# balise_mettrice_analogique.net
KiCad netlist of a schematic drawn in EAGLE
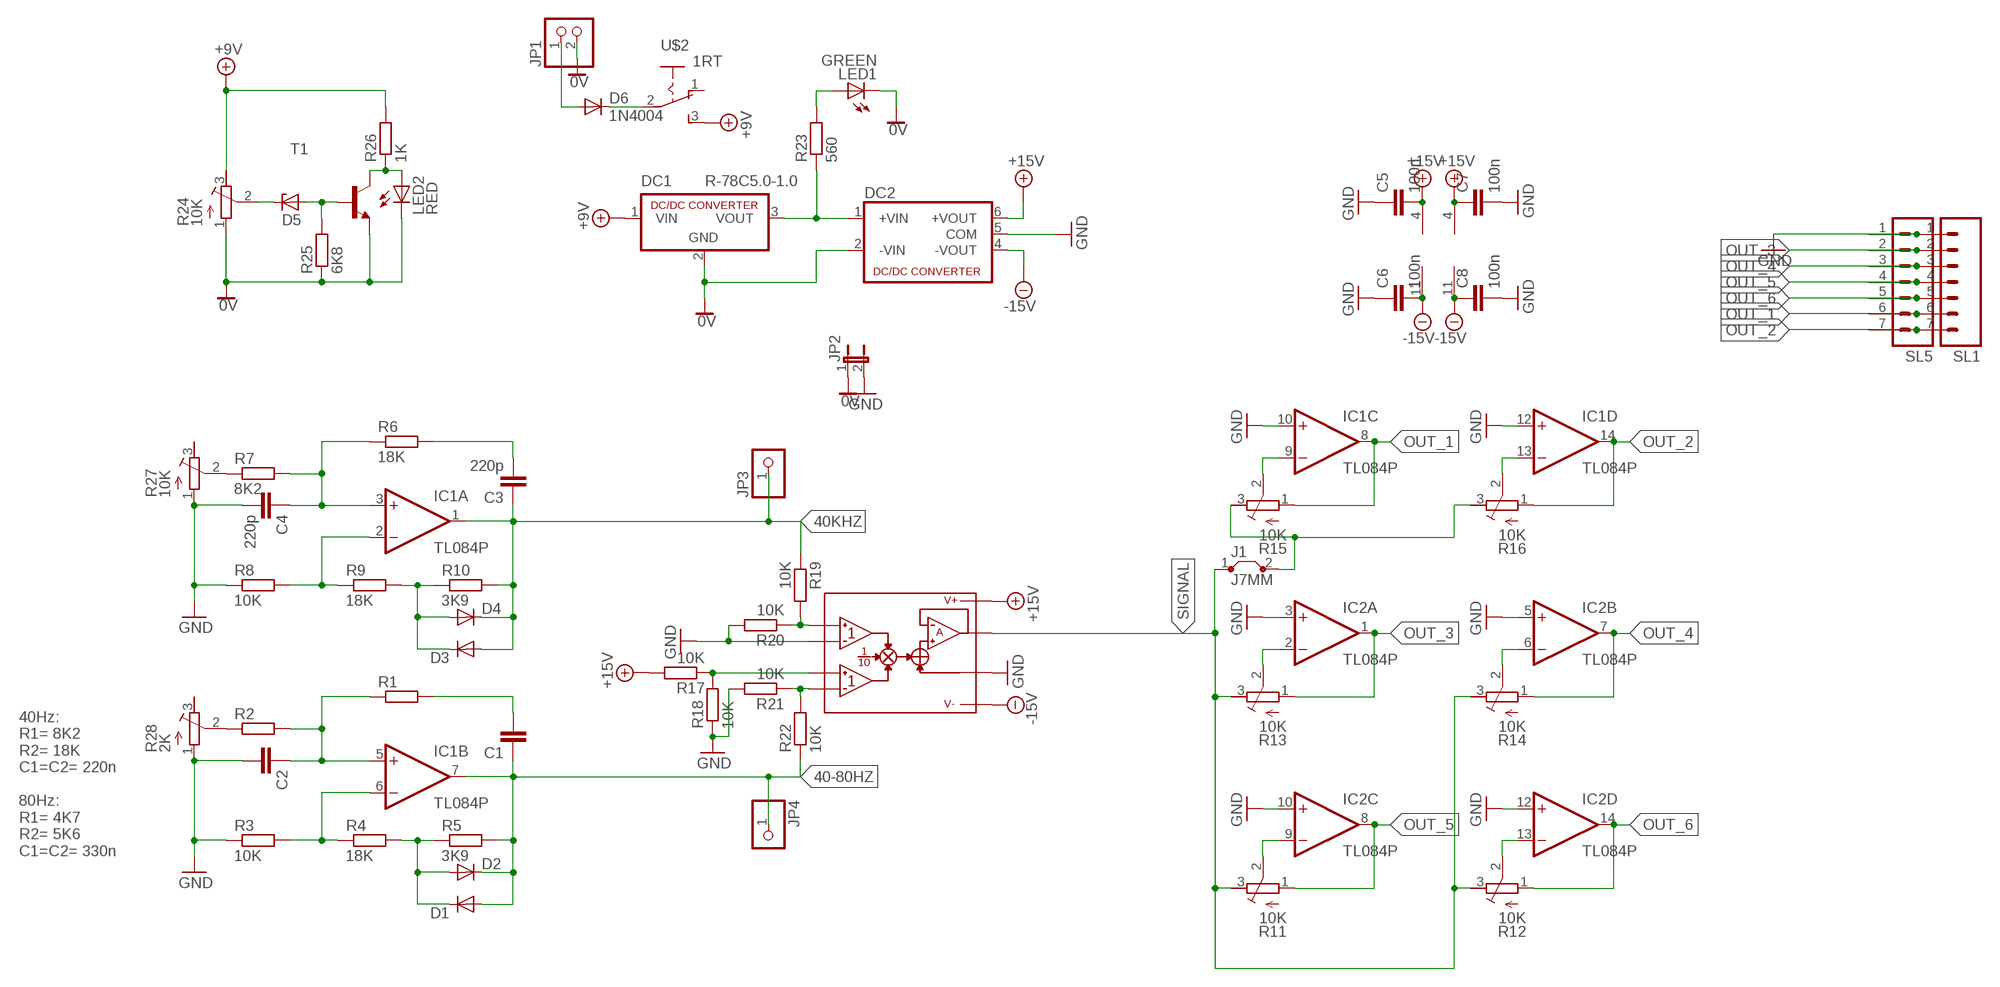
[diagram p0: schematic, sheet 1]

(export (version "E")
  (design (tool "Eeschema 10.0.6"))
  (components
    (comp (ref "C1")
      (value "C-EU075-032X103")
      (footprint "eagle-import:C075-032X103")
      (libsource (lib "eagle-import") (part "C-EU075-032X103"))
    )
    (comp (ref "C2")
      (value "C-EU075-032X103")
      (footprint "eagle-import:C075-032X103")
      (libsource (lib "eagle-import") (part "C-EU075-032X103"))
    )
    (comp (ref "C3")
      (value "220p")
      (footprint "eagle-import:C075-032X103")
      (fields (field (name "MF") "PANASONIC ELECTRONIC COMPONENTS") (field (name "MPN") "EEE1EA220SP"))
      (libsource (lib "eagle-import") (part "C-EU075-032X103"))
    )
    (comp (ref "C4")
      (value "220p")
      (footprint "eagle-import:C075-032X103")
      (fields (field (name "MF") "PANASONIC ELECTRONIC COMPONENTS") (field (name "MPN") "EEE1EA220SP"))
      (libsource (lib "eagle-import") (part "C-EU075-032X103"))
    )
    (comp (ref "C5")
      (value "100n")
      (footprint "eagle-import:C050-024X044")
      (libsource (lib "eagle-import") (part "C-EU050-024X044"))
    )
    (comp (ref "C6")
      (value "100n")
      (footprint "eagle-import:C050-024X044")
      (libsource (lib "eagle-import") (part "C-EU050-024X044"))
    )
    (comp (ref "C7")
      (value "100n")
      (footprint "eagle-import:C050-024X044")
      (libsource (lib "eagle-import") (part "C-EU050-024X044"))
    )
    (comp (ref "C8")
      (value "100n")
      (footprint "eagle-import:C050-024X044")
      (libsource (lib "eagle-import") (part "C-EU050-024X044"))
    )
    (comp (ref "D1")
      (value "DIODE-D-2.5")
      (footprint "eagle-import:D-2.5")
      (libsource (lib "eagle-import") (part "DIODE-D-2.5"))
    )
    (comp (ref "D2")
      (value "DIODE-D-2.5")
      (footprint "eagle-import:D-2.5")
      (libsource (lib "eagle-import") (part "DIODE-D-2.5"))
    )
    (comp (ref "D3")
      (value "DIODE-D-2.5")
      (footprint "eagle-import:D-2.5")
      (libsource (lib "eagle-import") (part "DIODE-D-2.5"))
    )
    (comp (ref "D4")
      (value "DIODE-D-2.5")
      (footprint "eagle-import:D-2.5")
      (libsource (lib "eagle-import") (part "DIODE-D-2.5"))
    )
    (comp (ref "D5")
      (value "ZENER-DIODEZD-2.5")
      (footprint "eagle-import:ZDIO-2.5")
      (libsource (lib "eagle-import") (part "ZENER-DIODEZD-2.5"))
    )
    (comp (ref "D6")
      (value "1N4004")
      (footprint "eagle-import:DO41-10")
      (libsource (lib "eagle-import") (part "1N4004"))
    )
    (comp (ref "DC1")
      (value "R-78C5.0-1.0")
      (footprint "eagle-import:SIP3")
      (libsource (lib "eagle-import") (part "R-78C-1.05.0"))
    )
    (comp (ref "DC2")
      (value "NMA")
      (footprint "eagle-import:NMA")
      (fields
        (field (name "MF") "C & D TECHNOLOGIES, INC")
        (field (name "MPN") "NMA0515SC")
        (field (name "MF_1") "MURATA POWER SOLUTIONS")
        (field (name "MPN_1") "NMA1205DC")
        (field (name "OC_FARNELL") "1021434")
      )
      (libsource (lib "eagle-import") (part "NMA"))
    )
    (comp (ref "IC1")
      (value "TL084P")
      (footprint "eagle-import:DIL14")
      (fields (field (name "OC_FARNELL") "unknown"))
      (libsource (lib "eagle-import") (part "TL084P"))
    )
    (comp (ref "IC2")
      (value "TL084P")
      (footprint "eagle-import:DIL14")
      (fields (field (name "OC_FARNELL") "unknown"))
      (libsource (lib "eagle-import") (part "TL084P"))
    )
    (comp (ref "J1")
      (value "J7MM")
      (footprint "eagle-import:07")
      (libsource (lib "eagle-import") (part "J7MM"))
    )
    (comp (ref "JP1")
      (value "PINHD-1X2")
      (footprint "eagle-import:1X02")
      (libsource (lib "eagle-import") (part "PINHD-1X2"))
    )
    (comp (ref "JP2")
      (value "JP1E")
      (footprint "eagle-import:JP1")
      (libsource (lib "eagle-import") (part "JP1E"))
    )
    (comp (ref "JP3")
      (value "PINHD-1X1")
      (footprint "eagle-import:1X01")
      (libsource (lib "eagle-import") (part "PINHD-1X1"))
    )
    (comp (ref "JP4")
      (value "PINHD-1X1")
      (footprint "eagle-import:1X01")
      (libsource (lib "eagle-import") (part "PINHD-1X1"))
    )
    (comp (ref "LED1")
      (value "GREEN")
      (footprint "eagle-import:Q62902-B155")
      (libsource (lib "eagle-import") (part "LEDB155"))
    )
    (comp (ref "LED2")
      (value "RED")
      (footprint "eagle-import:Q62902-B155")
      (libsource (lib "eagle-import") (part "LEDB155"))
    )
    (comp (ref "R1")
      (value "R-EU_0207/2V")
      (footprint "eagle-import:0207_2V")
      (libsource (lib "eagle-import") (part "R-EU_0207/2V"))
    )
    (comp (ref "R2")
      (value "R-EU_0204/7")
      (footprint "eagle-import:0204_7")
      (libsource (lib "eagle-import") (part "R-EU_0204/7"))
    )
    (comp (ref "R3")
      (value "10K")
      (footprint "eagle-import:0207_2V")
      (libsource (lib "eagle-import") (part "R-EU_0207/2V"))
    )
    (comp (ref "R4")
      (value "18K")
      (footprint "eagle-import:0207_2V")
      (libsource (lib "eagle-import") (part "R-EU_0207/2V"))
    )
    (comp (ref "R5")
      (value "3K9")
      (footprint "eagle-import:0207_2V")
      (libsource (lib "eagle-import") (part "R-EU_0207/2V"))
    )
    (comp (ref "R6")
      (value "18K")
      (footprint "eagle-import:0207_2V")
      (libsource (lib "eagle-import") (part "R-EU_0207/2V"))
    )
    (comp (ref "R7")
      (value "8K2")
      (footprint "eagle-import:0207_2V")
      (libsource (lib "eagle-import") (part "R-EU_0207/2V"))
    )
    (comp (ref "R8")
      (value "10K")
      (footprint "eagle-import:0207_2V")
      (libsource (lib "eagle-import") (part "R-EU_0207/2V"))
    )
    (comp (ref "R9")
      (value "18K")
      (footprint "eagle-import:0207_2V")
      (libsource (lib "eagle-import") (part "R-EU_0207/2V"))
    )
    (comp (ref "R10")
      (value "3K9")
      (footprint "eagle-import:0207_2V")
      (libsource (lib "eagle-import") (part "R-EU_0207/2V"))
    )
    (comp (ref "R11")
      (value "10K")
      (footprint "eagle-import:RTRIM3339P")
      (libsource (lib "eagle-import") (part "R-TRIMM3339P"))
    )
    (comp (ref "R12")
      (value "10K")
      (footprint "eagle-import:RTRIM3339P")
      (libsource (lib "eagle-import") (part "R-TRIMM3339P"))
    )
    (comp (ref "R13")
      (value "10K")
      (footprint "eagle-import:RTRIM3339P")
      (libsource (lib "eagle-import") (part "R-TRIMM3339P"))
    )
    (comp (ref "R14")
      (value "10K")
      (footprint "eagle-import:RTRIM3339P")
      (libsource (lib "eagle-import") (part "R-TRIMM3339P"))
    )
    (comp (ref "R15")
      (value "10K")
      (footprint "eagle-import:RTRIM3339P")
      (libsource (lib "eagle-import") (part "R-TRIMM3339P"))
    )
    (comp (ref "R16")
      (value "10K")
      (footprint "eagle-import:RTRIM3339P")
      (libsource (lib "eagle-import") (part "R-TRIMM3339P"))
    )
    (comp (ref "R17")
      (value "10K")
      (footprint "eagle-import:0207_2V")
      (libsource (lib "eagle-import") (part "R-EU_0207/2V"))
    )
    (comp (ref "R18")
      (value "10K")
      (footprint "eagle-import:0207_2V")
      (libsource (lib "eagle-import") (part "R-EU_0207/2V"))
    )
    (comp (ref "R19")
      (value "10K")
      (footprint "eagle-import:0207_2V")
      (libsource (lib "eagle-import") (part "R-EU_0207/2V"))
    )
    (comp (ref "R20")
      (value "10K")
      (footprint "eagle-import:0207_2V")
      (libsource (lib "eagle-import") (part "R-EU_0207/2V"))
    )
    (comp (ref "R21")
      (value "10K")
      (footprint "eagle-import:0207_2V")
      (libsource (lib "eagle-import") (part "R-EU_0207/2V"))
    )
    (comp (ref "R22")
      (value "10K")
      (footprint "eagle-import:0207_2V")
      (libsource (lib "eagle-import") (part "R-EU_0207/2V"))
    )
    (comp (ref "R23")
      (value "560")
      (footprint "eagle-import:0204_7")
      (libsource (lib "eagle-import") (part "R-EU_0204/7"))
    )
    (comp (ref "R24")
      (value "10K")
      (footprint "eagle-import:RTRIM3339P")
      (libsource (lib "eagle-import") (part "R-TRIMM3339P"))
    )
    (comp (ref "R25")
      (value "6K8")
      (footprint "eagle-import:0207_2V")
      (libsource (lib "eagle-import") (part "R-EU_0207/2V"))
    )
    (comp (ref "R26")
      (value "1K")
      (footprint "eagle-import:0207_2V")
      (libsource (lib "eagle-import") (part "R-EU_0207/2V"))
    )
    (comp (ref "R27")
      (value "10K")
      (footprint "eagle-import:RTRIM3339P")
      (libsource (lib "eagle-import") (part "R-TRIMM3339P"))
    )
    (comp (ref "R28")
      (value "2K")
      (footprint "eagle-import:RTRIM3339P")
      (libsource (lib "eagle-import") (part "R-TRIMM3339P"))
    )
    (comp (ref "SL1")
      (value "M07")
      (footprint "eagle-import:07P")
      (fields (field (name "OC_FARNELL") "unknown") (field (name "OC_NEWARK") "unknown"))
      (libsource (lib "eagle-import") (part "M07"))
    )
    (comp (ref "SL5")
      (value "M07")
      (footprint "eagle-import:07P")
      (fields (field (name "OC_FARNELL") "unknown"))
      (libsource (lib "eagle-import") (part "M07"))
    )
    (comp (ref "T1")
      (value "2N5400-NPN-TO92-CBE")
      (footprint "eagle-import:TO92-CBE")
      (libsource (lib "eagle-import") (part "-NPN-TO92-CBE2N5400"))
    )
    (comp (ref "U$1")
      (value "AD633JN")
      (footprint "eagle-import:DIL08")
      (libsource (lib "eagle-import") (part "AD633JN"))
    )
    (comp (ref "U$2")
      (value "1RT")
      (footprint "eagle-import:1RT")
      (libsource (lib "eagle-import") (part "1RT"))
    )
  )
  (nets
    (net (code "1") (name "+9V") (class "Default")
      (node (ref "DC1") (pin "1") (pinfunction "VIN_1") (pintype "passive"))
      (node (ref "R24") (pin "3") (pinfunction "A_3") (pintype "passive"))
      (node (ref "R26") (pin "2") (pinfunction "2_2") (pintype "passive"))
      (node (ref "U$2") (pin "3") (pinfunction "S_3") (pintype "passive"))
    )
    (net (code "2") (name "+15V") (class "Default")
      (node (ref "C5") (pin "2") (pinfunction "2_2") (pintype "passive"))
      (node (ref "C7") (pin "1") (pinfunction "1_1") (pintype "passive"))
      (node (ref "DC2") (pin "6") (pinfunction "+VOUT_6") (pintype "passive"))
      (node (ref "IC1") (pin "4") (pinfunction "V+_4") (pintype "power_in"))
      (node (ref "IC2") (pin "4") (pinfunction "V+_4") (pintype "power_in"))
      (node (ref "R17") (pin "2") (pinfunction "2_2") (pintype "passive"))
      (node (ref "U$1") (pin "8") (pinfunction "+V_8") (pintype "bidirectional"))
    )
    (net (code "3") (name "-15V") (class "Default")
      (node (ref "C6") (pin "2") (pinfunction "2_2") (pintype "passive"))
      (node (ref "C8") (pin "1") (pinfunction "1_1") (pintype "passive"))
      (node (ref "DC2") (pin "4") (pinfunction "-VOUT_4") (pintype "passive"))
      (node (ref "IC1") (pin "11") (pinfunction "V-_11") (pintype "power_in"))
      (node (ref "IC2") (pin "11") (pinfunction "V-_11") (pintype "power_in"))
      (node (ref "U$1") (pin "5") (pinfunction "-V_5") (pintype "bidirectional"))
    )
    (net (code "4") (name "0V") (class "Default")
      (node (ref "DC1") (pin "2") (pinfunction "GND_2") (pintype "passive"))
      (node (ref "DC2") (pin "2") (pinfunction "-VIN_2") (pintype "passive"))
      (node (ref "JP1") (pin "2") (pinfunction "2_2") (pintype "passive"))
      (node (ref "JP2") (pin "1") (pinfunction "1_1") (pintype "passive"))
      (node (ref "LED1") (pin "K") (pinfunction "C_K") (pintype "passive"))
      (node (ref "LED2") (pin "K") (pinfunction "C_K") (pintype "passive"))
      (node (ref "R24") (pin "1") (pinfunction "E_1") (pintype "passive"))
      (node (ref "R25") (pin "1") (pinfunction "1_1") (pintype "passive"))
      (node (ref "T1") (pin "E") (pinfunction "E_E") (pintype "passive"))
    )
    (net (code "5") (name "40-80HZ") (class "Default")
      (node (ref "C1") (pin "1") (pinfunction "1_1") (pintype "passive"))
      (node (ref "D1") (pin "A") (pinfunction "A_A") (pintype "passive"))
      (node (ref "D2") (pin "C") (pinfunction "C_C") (pintype "passive"))
      (node (ref "IC1") (pin "7") (pinfunction "OUT_7") (pintype "output"))
      (node (ref "JP4") (pin "1") (pinfunction "1_1") (pintype "passive"))
      (node (ref "R22") (pin "1") (pinfunction "1_1") (pintype "passive"))
      (node (ref "R5") (pin "2") (pinfunction "2_2") (pintype "passive"))
    )
    (net (code "6") (name "40KHZ") (class "Default")
      (node (ref "C3") (pin "1") (pinfunction "1_1") (pintype "passive"))
      (node (ref "D3") (pin "A") (pinfunction "A_A") (pintype "passive"))
      (node (ref "D4") (pin "C") (pinfunction "C_C") (pintype "passive"))
      (node (ref "IC1") (pin "1") (pinfunction "OUT_1") (pintype "output"))
      (node (ref "JP3") (pin "1") (pinfunction "1_1") (pintype "passive"))
      (node (ref "R10") (pin "2") (pinfunction "2_2") (pintype "passive"))
      (node (ref "R19") (pin "1") (pinfunction "1_1") (pintype "passive"))
    )
    (net (code "7") (name "GND") (class "Default")
      (node (ref "C2") (pin "2") (pinfunction "2_2") (pintype "passive"))
      (node (ref "C4") (pin "2") (pinfunction "2_2") (pintype "passive"))
      (node (ref "C5") (pin "1") (pinfunction "1_1") (pintype "passive"))
      (node (ref "C6") (pin "1") (pinfunction "1_1") (pintype "passive"))
      (node (ref "C7") (pin "2") (pinfunction "2_2") (pintype "passive"))
      (node (ref "C8") (pin "2") (pinfunction "2_2") (pintype "passive"))
      (node (ref "DC2") (pin "5") (pinfunction "COM_5") (pintype "passive"))
      (node (ref "IC1") (pin "10") (pinfunction "+IN_10") (pintype "input"))
      (node (ref "IC1") (pin "12") (pinfunction "+IN_12") (pintype "input"))
      (node (ref "IC2") (pin "10") (pinfunction "+IN_10") (pintype "input"))
      (node (ref "IC2") (pin "12") (pinfunction "+IN_12") (pintype "input"))
      (node (ref "IC2") (pin "3") (pinfunction "+IN_3") (pintype "input"))
      (node (ref "IC2") (pin "5") (pinfunction "+IN_5") (pintype "input"))
      (node (ref "JP2") (pin "2") (pinfunction "2_2") (pintype "passive"))
      (node (ref "R18") (pin "1") (pinfunction "1_1") (pintype "passive"))
      (node (ref "R20") (pin "2") (pinfunction "2_2") (pintype "passive"))
      (node (ref "R21") (pin "2") (pinfunction "2_2") (pintype "passive"))
      (node (ref "R27") (pin "1") (pinfunction "E_1") (pintype "passive"))
      (node (ref "R28") (pin "1") (pinfunction "E_1") (pintype "passive"))
      (node (ref "R3") (pin "1") (pinfunction "1_1") (pintype "passive"))
      (node (ref "R8") (pin "1") (pinfunction "1_1") (pintype "passive"))
      (node (ref "SL1") (pin "1") (pinfunction "1_1") (pintype "passive"))
      (node (ref "SL5") (pin "1") (pinfunction "1_1") (pintype "passive"))
      (node (ref "U$1") (pin "2") (pinfunction "X2_2") (pintype "bidirectional"))
      (node (ref "U$1") (pin "6") (pinfunction "Z_6") (pintype "bidirectional"))
    )
    (net (code "8") (name "Net-(C1-Pad2)") (class "Default")
      (node (ref "C1") (pin "2") (pinfunction "2_2") (pintype "passive"))
      (node (ref "R1") (pin "2") (pinfunction "2_2") (pintype "passive"))
    )
    (net (code "9") (name "Net-(C3-Pad2)") (class "Default")
      (node (ref "C3") (pin "2") (pinfunction "2_2") (pintype "passive"))
      (node (ref "R6") (pin "2") (pinfunction "2_2") (pintype "passive"))
    )
    (net (code "10") (name "Net-(D1-PadC)") (class "Default")
      (node (ref "D1") (pin "C") (pinfunction "C_C") (pintype "passive"))
      (node (ref "D2") (pin "A") (pinfunction "A_A") (pintype "passive"))
      (node (ref "R4") (pin "2") (pinfunction "2_2") (pintype "passive"))
      (node (ref "R5") (pin "1") (pinfunction "1_1") (pintype "passive"))
    )
    (net (code "11") (name "Net-(D3-PadC)") (class "Default")
      (node (ref "D3") (pin "C") (pinfunction "C_C") (pintype "passive"))
      (node (ref "D4") (pin "A") (pinfunction "A_A") (pintype "passive"))
      (node (ref "R10") (pin "1") (pinfunction "1_1") (pintype "passive"))
      (node (ref "R9") (pin "2") (pinfunction "2_2") (pintype "passive"))
    )
    (net (code "12") (name "Net-(D5-PadA)") (class "Default")
      (node (ref "D5") (pin "A") (pinfunction "A_A") (pintype "passive"))
      (node (ref "R25") (pin "2") (pinfunction "2_2") (pintype "passive"))
      (node (ref "T1") (pin "B") (pinfunction "B_B") (pintype "passive"))
    )
    (net (code "13") (name "Net-(D6-PadA)") (class "Default")
      (node (ref "D6") (pin "A") (pinfunction "A_A") (pintype "passive"))
      (node (ref "JP1") (pin "1") (pinfunction "1_1") (pintype "passive"))
    )
    (net (code "14") (name "Net-(DC1-VOUT)") (class "Default")
      (node (ref "DC1") (pin "3") (pinfunction "VOUT_3") (pintype "passive"))
      (node (ref "DC2") (pin "1") (pinfunction "+VIN_1") (pintype "passive"))
      (node (ref "R23") (pin "1") (pinfunction "1_1") (pintype "passive"))
    )
    (net (code "15") (name "Net-(IC1A-+IN)") (class "Default")
      (node (ref "C4") (pin "1") (pinfunction "1_1") (pintype "passive"))
      (node (ref "IC1") (pin "3") (pinfunction "+IN_3") (pintype "input"))
      (node (ref "R6") (pin "1") (pinfunction "1_1") (pintype "passive"))
      (node (ref "R7") (pin "2") (pinfunction "2_2") (pintype "passive"))
    )
    (net (code "16") (name "Net-(IC1A--IN)") (class "Default")
      (node (ref "IC1") (pin "2") (pinfunction "-IN_2") (pintype "input"))
      (node (ref "R8") (pin "2") (pinfunction "2_2") (pintype "passive"))
      (node (ref "R9") (pin "1") (pinfunction "1_1") (pintype "passive"))
    )
    (net (code "17") (name "Net-(IC1B-+IN)") (class "Default")
      (node (ref "C2") (pin "1") (pinfunction "1_1") (pintype "passive"))
      (node (ref "IC1") (pin "5") (pinfunction "+IN_5") (pintype "input"))
      (node (ref "R1") (pin "1") (pinfunction "1_1") (pintype "passive"))
      (node (ref "R2") (pin "2") (pinfunction "2_2") (pintype "passive"))
    )
    (net (code "18") (name "Net-(IC1B--IN)") (class "Default")
      (node (ref "IC1") (pin "6") (pinfunction "-IN_6") (pintype "input"))
      (node (ref "R3") (pin "2") (pinfunction "2_2") (pintype "passive"))
      (node (ref "R4") (pin "1") (pinfunction "1_1") (pintype "passive"))
    )
    (net (code "19") (name "Net-(IC1C--IN)") (class "Default")
      (node (ref "IC1") (pin "9") (pinfunction "-IN_9") (pintype "input"))
      (node (ref "R15") (pin "2") (pinfunction "S_2") (pintype "passive"))
    )
    (net (code "20") (name "Net-(IC1D--IN)") (class "Default")
      (node (ref "IC1") (pin "13") (pinfunction "-IN_13") (pintype "input"))
      (node (ref "R16") (pin "2") (pinfunction "S_2") (pintype "passive"))
    )
    (net (code "21") (name "Net-(IC2A--IN)") (class "Default")
      (node (ref "IC2") (pin "2") (pinfunction "-IN_2") (pintype "input"))
      (node (ref "R13") (pin "2") (pinfunction "S_2") (pintype "passive"))
    )
    (net (code "22") (name "Net-(IC2B--IN)") (class "Default")
      (node (ref "IC2") (pin "6") (pinfunction "-IN_6") (pintype "input"))
      (node (ref "R14") (pin "2") (pinfunction "S_2") (pintype "passive"))
    )
    (net (code "23") (name "Net-(IC2C--IN)") (class "Default")
      (node (ref "IC2") (pin "9") (pinfunction "-IN_9") (pintype "input"))
      (node (ref "R11") (pin "2") (pinfunction "S_2") (pintype "passive"))
    )
    (net (code "24") (name "Net-(IC2D--IN)") (class "Default")
      (node (ref "IC2") (pin "13") (pinfunction "-IN_13") (pintype "input"))
      (node (ref "R12") (pin "2") (pinfunction "S_2") (pintype "passive"))
    )
    (net (code "25") (name "Net-(LED1-PadA)") (class "Default")
      (node (ref "LED1") (pin "A") (pinfunction "A_A") (pintype "passive"))
      (node (ref "R23") (pin "2") (pinfunction "2_2") (pintype "passive"))
    )
    (net (code "26") (name "Net-(LED2-PadA)") (class "Default")
      (node (ref "LED2") (pin "A") (pinfunction "A_A") (pintype "passive"))
      (node (ref "R26") (pin "1") (pinfunction "1_1") (pintype "passive"))
      (node (ref "T1") (pin "C") (pinfunction "C_C") (pintype "passive"))
    )
    (net (code "27") (name "Net-(R15-A)") (class "Default")
      (node (ref "J1") (pin "2") (pinfunction "2_2") (pintype "passive"))
      (node (ref "R15") (pin "3") (pinfunction "A_3") (pintype "passive"))
      (node (ref "R16") (pin "3") (pinfunction "A_3") (pintype "passive"))
    )
    (net (code "28") (name "Net-(R24-S)") (class "Default")
      (node (ref "D5") (pin "C") (pinfunction "C_C") (pintype "passive"))
      (node (ref "R24") (pin "2") (pinfunction "S_2") (pintype "passive"))
    )
    (net (code "29") (name "Net-(R27-S)") (class "Default")
      (node (ref "R27") (pin "2") (pinfunction "S_2") (pintype "passive"))
      (node (ref "R7") (pin "1") (pinfunction "1_1") (pintype "passive"))
    )
    (net (code "30") (name "Net-(R28-S)") (class "Default")
      (node (ref "R2") (pin "1") (pinfunction "1_1") (pintype "passive"))
      (node (ref "R28") (pin "2") (pinfunction "S_2") (pintype "passive"))
    )
    (net (code "31") (name "Net-(U$1-X1)") (class "Default")
      (node (ref "R19") (pin "2") (pinfunction "2_2") (pintype "passive"))
      (node (ref "R20") (pin "1") (pinfunction "1_1") (pintype "passive"))
      (node (ref "U$1") (pin "1") (pinfunction "X1_1") (pintype "bidirectional"))
    )
    (net (code "32") (name "Net-(U$1-Y1)") (class "Default")
      (node (ref "R17") (pin "1") (pinfunction "1_1") (pintype "passive"))
      (node (ref "R18") (pin "2") (pinfunction "2_2") (pintype "passive"))
      (node (ref "U$1") (pin "3") (pinfunction "Y1_3") (pintype "bidirectional"))
    )
    (net (code "33") (name "Net-(U$1-Y2)") (class "Default")
      (node (ref "R21") (pin "1") (pinfunction "1_1") (pintype "passive"))
      (node (ref "R22") (pin "2") (pinfunction "2_2") (pintype "passive"))
      (node (ref "U$1") (pin "4") (pinfunction "Y2_4") (pintype "bidirectional"))
    )
    (net (code "34") (name "Net-(U$2-P)") (class "Default")
      (node (ref "D6") (pin "C") (pinfunction "C_C") (pintype "passive"))
      (node (ref "U$2") (pin "2") (pinfunction "P_2") (pintype "passive"))
    )
    (net (code "35") (name "OUT_1") (class "Default")
      (node (ref "IC1") (pin "8") (pinfunction "OUT_8") (pintype "output"))
      (node (ref "R15") (pin "1") (pinfunction "E_1") (pintype "passive"))
      (node (ref "SL1") (pin "6") (pinfunction "6_6") (pintype "passive"))
      (node (ref "SL5") (pin "6") (pinfunction "6_6") (pintype "passive"))
    )
    (net (code "36") (name "OUT_2") (class "Default")
      (node (ref "IC1") (pin "14") (pinfunction "OUT_14") (pintype "output"))
      (node (ref "R16") (pin "1") (pinfunction "E_1") (pintype "passive"))
      (node (ref "SL1") (pin "7") (pinfunction "7_7") (pintype "passive"))
      (node (ref "SL5") (pin "7") (pinfunction "7_7") (pintype "passive"))
    )
    (net (code "37") (name "OUT_3") (class "Default")
      (node (ref "IC2") (pin "1") (pinfunction "OUT_1") (pintype "output"))
      (node (ref "R13") (pin "1") (pinfunction "E_1") (pintype "passive"))
      (node (ref "SL1") (pin "2") (pinfunction "2_2") (pintype "passive"))
      (node (ref "SL5") (pin "2") (pinfunction "2_2") (pintype "passive"))
    )
    (net (code "38") (name "OUT_4") (class "Default")
      (node (ref "IC2") (pin "7") (pinfunction "OUT_7") (pintype "output"))
      (node (ref "R14") (pin "1") (pinfunction "E_1") (pintype "passive"))
      (node (ref "SL1") (pin "3") (pinfunction "3_3") (pintype "passive"))
      (node (ref "SL5") (pin "3") (pinfunction "3_3") (pintype "passive"))
    )
    (net (code "39") (name "OUT_5") (class "Default")
      (node (ref "IC2") (pin "8") (pinfunction "OUT_8") (pintype "output"))
      (node (ref "R11") (pin "1") (pinfunction "E_1") (pintype "passive"))
      (node (ref "SL1") (pin "4") (pinfunction "4_4") (pintype "passive"))
      (node (ref "SL5") (pin "4") (pinfunction "4_4") (pintype "passive"))
    )
    (net (code "40") (name "OUT_6") (class "Default")
      (node (ref "IC2") (pin "14") (pinfunction "OUT_14") (pintype "output"))
      (node (ref "R12") (pin "1") (pinfunction "E_1") (pintype "passive"))
      (node (ref "SL1") (pin "5") (pinfunction "5_5") (pintype "passive"))
      (node (ref "SL5") (pin "5") (pinfunction "5_5") (pintype "passive"))
    )
    (net (code "41") (name "SIGNAL") (class "Default")
      (node (ref "J1") (pin "1") (pinfunction "1_1") (pintype "passive"))
      (node (ref "R11") (pin "3") (pinfunction "A_3") (pintype "passive"))
      (node (ref "R12") (pin "3") (pinfunction "A_3") (pintype "passive"))
      (node (ref "R13") (pin "3") (pinfunction "A_3") (pintype "passive"))
      (node (ref "R14") (pin "3") (pinfunction "A_3") (pintype "passive"))
      (node (ref "U$1") (pin "7") (pinfunction "W_7") (pintype "bidirectional"))
    )
    (net (code "42") (name "unconnected-(R27-A-Pad3)") (class "Default")
      (node (ref "R27") (pin "3") (pinfunction "A_3") (pintype "passive"))
    )
    (net (code "43") (name "unconnected-(R28-A-Pad3)") (class "Default")
      (node (ref "R28") (pin "3") (pinfunction "A_3") (pintype "passive"))
    )
    (net (code "44") (name "unconnected-(U$2-O-Pad1)") (class "Default")
      (node (ref "U$2") (pin "1") (pinfunction "O_1") (pintype "passive"))
    )
  )
)
